# phi-brain4ch.net
KiCad netlist of a schematic drawn in EAGLE
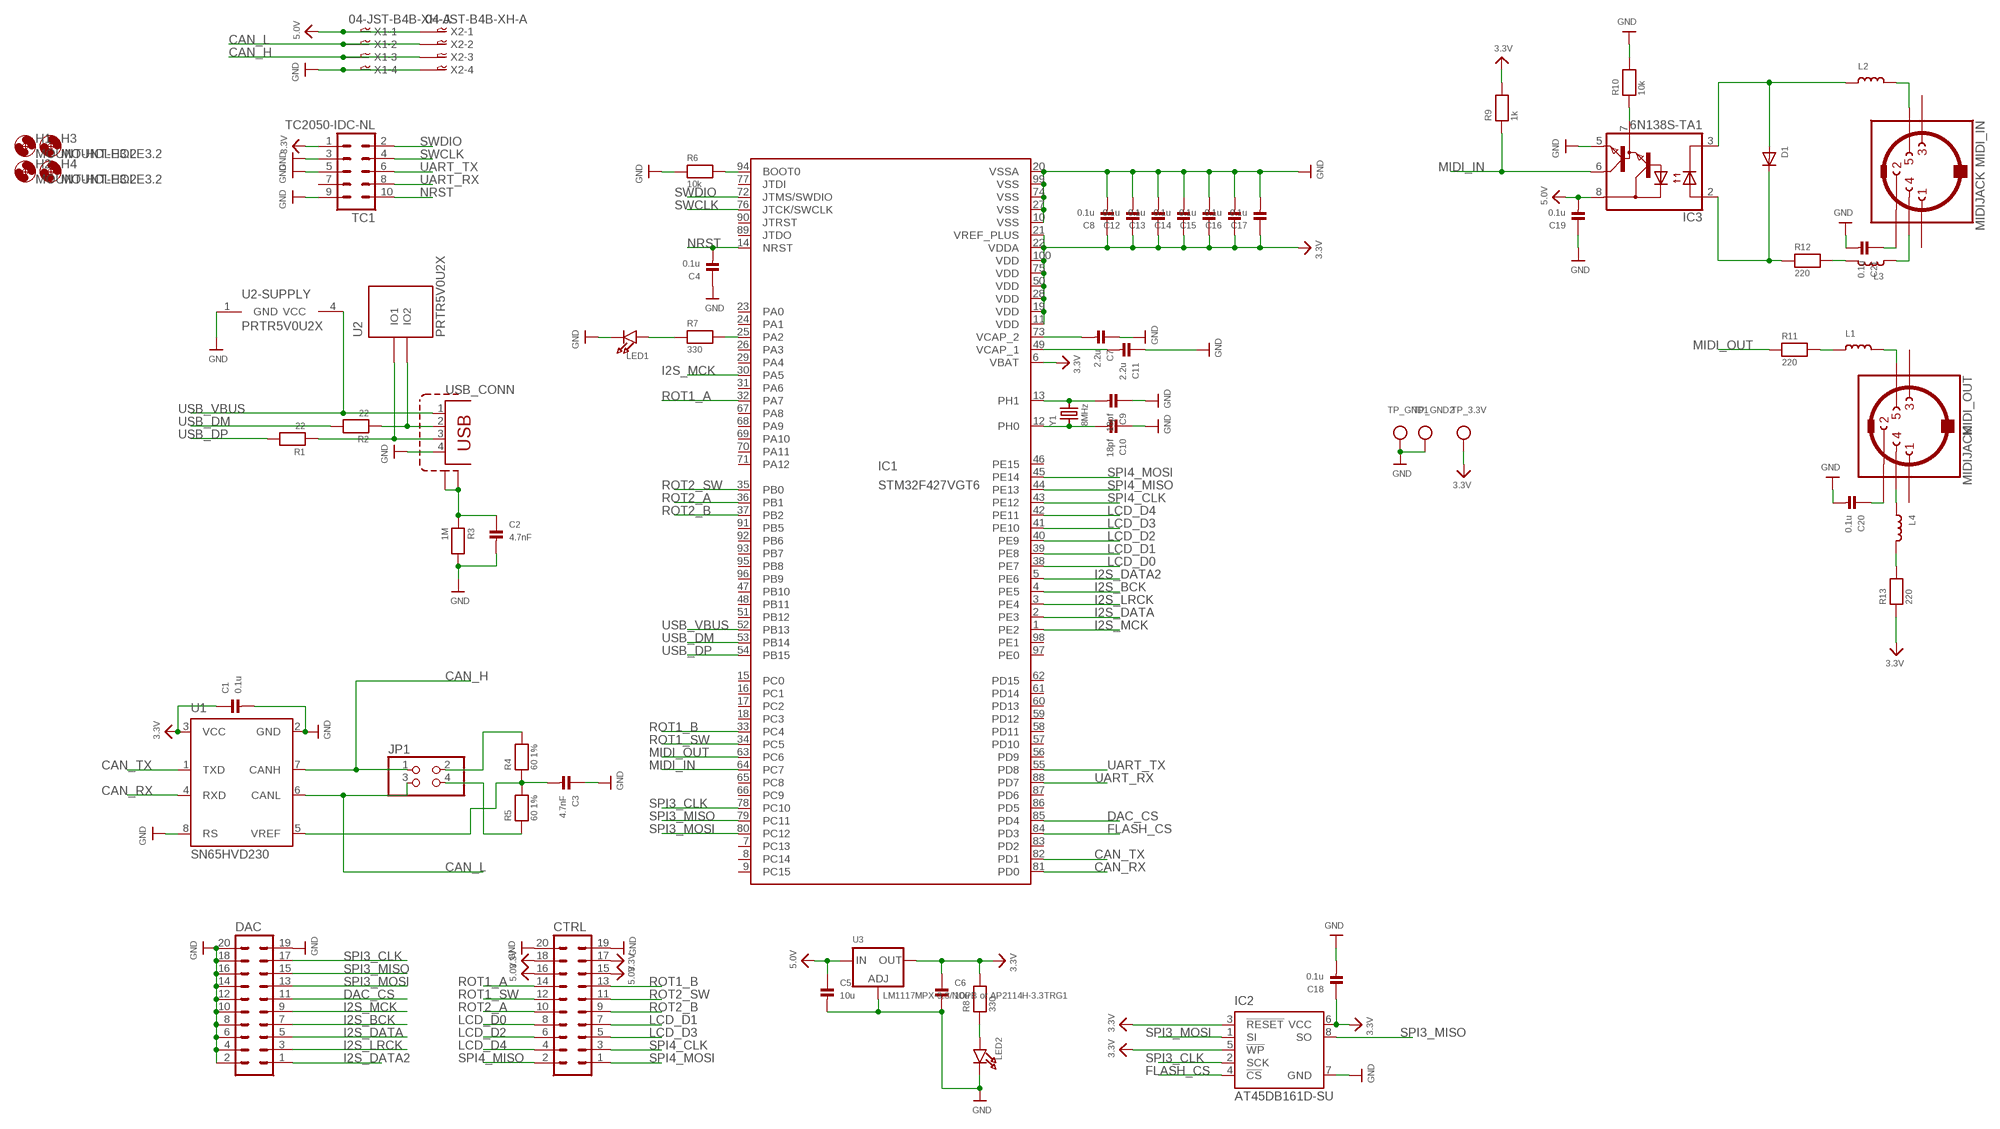
[diagram p0: schematic, sheet 1]

(export (version "E")
  (design (tool "Eeschema 10.0.6"))
  (components
    (comp (ref "C1")
      (value "0.1u")
      (footprint "eagle-import:0603")
      (fields (field (name "PARTNO") "0805DD104KAT2A"))
      (libsource (lib "eagle-import") (part "CAP_CERAMIC0603"))
    )
    (comp (ref "C2")
      (value "4.7nF")
      (footprint "eagle-import:0805")
      (fields (field (name "PARTNO") "885012207090"))
      (libsource (lib "eagle-import") (part "CAP_CERAMIC0805"))
    )
    (comp (ref "C3")
      (value "4.7nF")
      (footprint "eagle-import:0805")
      (fields (field (name "PARTNO") "885012207090"))
      (libsource (lib "eagle-import") (part "CAP_CERAMIC0805"))
    )
    (comp (ref "C4")
      (value "0.1u")
      (footprint "eagle-import:0603")
      (fields (field (name "PARTNO") "0805DD104KAT2A"))
      (libsource (lib "eagle-import") (part "CAP_CERAMIC0603"))
    )
    (comp (ref "C5")
      (value "10u")
      (footprint "eagle-import:0805")
      (fields (field (name "PARTNO") "81-GRM21BR6YA106KE3L"))
      (libsource (lib "eagle-import") (part "CAP_CERAMIC0805"))
    )
    (comp (ref "C6")
      (value "10u")
      (footprint "eagle-import:0805")
      (fields (field (name "PARTNO") "81-GRM21BR6YA106KE3L"))
      (libsource (lib "eagle-import") (part "CAP_CERAMIC0805"))
    )
    (comp (ref "C7")
      (value "2.2u")
      (footprint "eagle-import:0805")
      (fields (field (name "PARTNO") "581-08053D225MAT2A"))
      (libsource (lib "eagle-import") (part "CAP_CERAMIC0805"))
    )
    (comp (ref "C8")
      (value "0.1u")
      (footprint "eagle-import:0603")
      (fields (field (name "PARTNO") "0805DD104KAT2A"))
      (libsource (lib "eagle-import") (part "CAP_CERAMIC0603"))
    )
    (comp (ref "C9")
      (value "18pf")
      (footprint "eagle-import:0805")
      (fields (field (name "PARTNO") "C0805C180M3GACTU"))
      (libsource (lib "eagle-import") (part "CAP_CERAMIC0805"))
    )
    (comp (ref "C10")
      (value "18pf")
      (footprint "eagle-import:0805")
      (fields (field (name "PARTNO") "C0805C180M3GACTU"))
      (libsource (lib "eagle-import") (part "CAP_CERAMIC0805"))
    )
    (comp (ref "C11")
      (value "2.2u")
      (footprint "eagle-import:0805")
      (fields (field (name "PARTNO") "581-08053D225MAT2A"))
      (libsource (lib "eagle-import") (part "CAP_CERAMIC0805"))
    )
    (comp (ref "C12")
      (value "0.1u")
      (footprint "eagle-import:0603")
      (fields (field (name "PARTNO") "0805DD104KAT2A"))
      (libsource (lib "eagle-import") (part "CAP_CERAMIC0603"))
    )
    (comp (ref "C13")
      (value "0.1u")
      (footprint "eagle-import:0603")
      (fields (field (name "PARTNO") "0805DD104KAT2A"))
      (libsource (lib "eagle-import") (part "CAP_CERAMIC0603"))
    )
    (comp (ref "C14")
      (value "0.1u")
      (footprint "eagle-import:0603")
      (fields (field (name "PARTNO") "0805DD104KAT2A"))
      (libsource (lib "eagle-import") (part "CAP_CERAMIC0603"))
    )
    (comp (ref "C15")
      (value "0.1u")
      (footprint "eagle-import:0603")
      (fields (field (name "PARTNO") "0805DD104KAT2A"))
      (libsource (lib "eagle-import") (part "CAP_CERAMIC0603"))
    )
    (comp (ref "C16")
      (value "0.1u")
      (footprint "eagle-import:0603")
      (fields (field (name "PARTNO") "0805DD104KAT2A"))
      (libsource (lib "eagle-import") (part "CAP_CERAMIC0603"))
    )
    (comp (ref "C17")
      (value "0.1u")
      (footprint "eagle-import:0603")
      (fields (field (name "PARTNO") "0805DD104KAT2A"))
      (libsource (lib "eagle-import") (part "CAP_CERAMIC0603"))
    )
    (comp (ref "C18")
      (value "0.1u")
      (footprint "eagle-import:0603")
      (fields (field (name "PARTNO") "0805DD104KAT2A"))
      (libsource (lib "eagle-import") (part "CAP_CERAMIC0603"))
    )
    (comp (ref "C19")
      (value "0.1u")
      (footprint "eagle-import:0603")
      (fields (field (name "PARTNO") "0805DD104KAT2A"))
      (libsource (lib "eagle-import") (part "CAP_CERAMIC0603"))
    )
    (comp (ref "C20")
      (value "0.1u")
      (footprint "eagle-import:0603")
      (fields (field (name "PARTNO") "0805DD104KAT2A"))
      (libsource (lib "eagle-import") (part "CAP_CERAMIC0603"))
    )
    (comp (ref "C21")
      (value "0.1u")
      (footprint "eagle-import:0603")
      (fields (field (name "PARTNO") "0805DD104KAT2A"))
      (libsource (lib "eagle-import") (part "CAP_CERAMIC0603"))
    )
    (comp (ref "CTRL")
      (value "ML20")
      (footprint "eagle-import:ML20")
      (fields (field (name "PARTNO") "61202021621"))
      (libsource (lib "eagle-import") (part "ML20"))
    )
    (comp (ref "D1")
      (value "DIODESOD-123")
      (footprint "eagle-import:SOD-123")
      (fields (field (name "PARTNO") "MBR120"))
      (libsource (lib "eagle-import") (part "DIODESOD-123"))
    )
    (comp (ref "DAC")
      (value "ML20")
      (footprint "eagle-import:ML20")
      (fields (field (name "PARTNO") "61202021621"))
      (libsource (lib "eagle-import") (part "ML20"))
    )
    (comp (ref "H1")
      (value "MOUNT-HOLE3.2")
      (footprint "eagle-import:3,2")
      (libsource (lib "eagle-import") (part "MOUNT-HOLE3.2"))
    )
    (comp (ref "H2")
      (value "MOUNT-HOLE3.2")
      (footprint "eagle-import:3,2")
      (libsource (lib "eagle-import") (part "MOUNT-HOLE3.2"))
    )
    (comp (ref "H3")
      (value "MOUNT-HOLE3.2")
      (footprint "eagle-import:3,2")
      (libsource (lib "eagle-import") (part "MOUNT-HOLE3.2"))
    )
    (comp (ref "H4")
      (value "MOUNT-HOLE3.2")
      (footprint "eagle-import:3,2")
      (libsource (lib "eagle-import") (part "MOUNT-HOLE3.2"))
    )
    (comp (ref "IC1")
      (value "STM32F427VGT6")
      (footprint "eagle-import:TQFP100")
      (libsource (lib "eagle-import") (part "STM32F42X_43X_LQFP100"))
    )
    (comp (ref "IC2")
      (value "AT45DB161D-SU")
      (footprint "eagle-import:8S2")
      (fields (field (name "MF") "ATMEL"))
      (libsource (lib "eagle-import") (part "AT45DB161D-SU"))
    )
    (comp (ref "IC3")
      (value "6N138S-TA1")
      (footprint "eagle-import:SO8-GW300")
      (fields (field (name "PARTNO") "6N138S"))
      (libsource (lib "eagle-import") (part "6N138SMD"))
    )
    (comp (ref "JP1")
      (value "PINHD-2X2")
      (footprint "eagle-import:2X02")
      (fields (field (name "MPN") "5-146254-2"))
      (libsource (lib "eagle-import") (part "PINHD-2X2"))
    )
    (comp (ref "L1")
      (value "INDUCTOR0805")
      (footprint "eagle-import:0805")
      (fields (field (name "PARTNO") "70-ILHB0805ER601V"))
      (libsource (lib "eagle-import") (part "INDUCTOR0805"))
    )
    (comp (ref "L2")
      (value "INDUCTOR0805")
      (footprint "eagle-import:0805")
      (fields (field (name "PARTNO") "70-ILHB0805ER601V"))
      (libsource (lib "eagle-import") (part "INDUCTOR0805"))
    )
    (comp (ref "L3")
      (value "INDUCTOR0805")
      (footprint "eagle-import:0805")
      (fields (field (name "PARTNO") "70-ILHB0805ER601V"))
      (libsource (lib "eagle-import") (part "INDUCTOR0805"))
    )
    (comp (ref "L4")
      (value "INDUCTOR0805")
      (footprint "eagle-import:0805")
      (fields (field (name "PARTNO") "70-ILHB0805ER601V"))
      (libsource (lib "eagle-import") (part "INDUCTOR0805"))
    )
    (comp (ref "LED1")
      (value "LED0805")
      (footprint "eagle-import:CHIPLED_0805")
      (fields (field (name "PARTNO") "604-APT2012YC"))
      (libsource (lib "eagle-import") (part "LED0805"))
    )
    (comp (ref "LED2")
      (value "LED0805")
      (footprint "eagle-import:CHIPLED_0805")
      (fields (field (name "PARTNO") "604-APT2012YC"))
      (libsource (lib "eagle-import") (part "LED0805"))
    )
    (comp (ref "MIDI_IN")
      (value "MIDIJACK")
      (footprint "eagle-import:CP-2350")
      (libsource (lib "eagle-import") (part "MIDIJACK"))
    )
    (comp (ref "MIDI_OUT")
      (value "MIDIJACK")
      (footprint "eagle-import:CP-2350")
      (libsource (lib "eagle-import") (part "MIDIJACK"))
    )
    (comp (ref "R1")
      (value "22")
      (footprint "eagle-import:0805")
      (fields (field (name "MPN") "MF-RES-0603-22") (field (name "PARTNO") "ERJ-6ENF22R0V"))
      (libsource (lib "eagle-import") (part "RESISTOR0805"))
    )
    (comp (ref "R2")
      (value "22")
      (footprint "eagle-import:0805")
      (fields (field (name "MPN") "MF-RES-0603-22") (field (name "PARTNO") "ERJ-6ENF22R0V"))
      (libsource (lib "eagle-import") (part "RESISTOR0805"))
    )
    (comp (ref "R3")
      (value "1M")
      (footprint "eagle-import:0805")
      (fields (field (name "PARTNO") "AS08J1004ET"))
      (libsource (lib "eagle-import") (part "RESISTOR0805"))
    )
    (comp (ref "R4")
      (value "60 1%")
      (footprint "eagle-import:0805")
      (fields (field (name "MPN") "MF-RES-0603-60.4") (field (name "PARTNO") "ERJ-6ENF60R4V"))
      (libsource (lib "eagle-import") (part "RESISTOR0805"))
    )
    (comp (ref "R5")
      (value "60 1%")
      (footprint "eagle-import:0805")
      (fields (field (name "MPN") "MF-RES-0603-60.4") (field (name "PARTNO") "ERJ-6ENF60R4V"))
      (libsource (lib "eagle-import") (part "RESISTOR0805"))
    )
    (comp (ref "R6")
      (value "10k")
      (footprint "eagle-import:0805")
      (fields (field (name "PARTNO") "RC0805FR-0710KL"))
      (libsource (lib "eagle-import") (part "RESISTOR0805"))
    )
    (comp (ref "R7")
      (value "330")
      (footprint "eagle-import:0805")
      (fields (field (name "MPN") "MF-RES-0603-330") (field (name "PARTNO") "CPF0805B330RE1"))
      (libsource (lib "eagle-import") (part "RESISTOR0805"))
    )
    (comp (ref "R8")
      (value "330")
      (footprint "eagle-import:0805")
      (fields (field (name "MPN") "MF-RES-0603-330") (field (name "PARTNO") "CPF0805B330RE1"))
      (libsource (lib "eagle-import") (part "RESISTOR0805"))
    )
    (comp (ref "R9")
      (value "1k")
      (footprint "eagle-import:0805")
      (fields (field (name "PARTNO") "AS08J1001ET"))
      (libsource (lib "eagle-import") (part "RESISTOR0805"))
    )
    (comp (ref "R10")
      (value "10k")
      (footprint "eagle-import:0805")
      (fields (field (name "PARTNO") "RC0805FR-0710KL"))
      (libsource (lib "eagle-import") (part "RESISTOR0805"))
    )
    (comp (ref "R11")
      (value "220")
      (footprint "eagle-import:0805")
      (fields (field (name "PARTNO") "ERJ-6GEYJ221V"))
      (libsource (lib "eagle-import") (part "RESISTOR0805"))
    )
    (comp (ref "R12")
      (value "220")
      (footprint "eagle-import:0805")
      (fields (field (name "PARTNO") "ERJ-6GEYJ221V"))
      (libsource (lib "eagle-import") (part "RESISTOR0805"))
    )
    (comp (ref "R13")
      (value "220")
      (footprint "eagle-import:0805")
      (fields (field (name "PARTNO") "ERJ-6GEYJ221V"))
      (libsource (lib "eagle-import") (part "RESISTOR0805"))
    )
    (comp (ref "TC1")
      (value "TC2050-IDC-NL")
      (footprint "eagle-import:TC2050-IDC-NL")
      (libsource (lib "eagle-import") (part "TC2050-IDC-NL"))
    )
    (comp (ref "TP_3.3V")
      (value "TESTPOINT0.1\"")
      (footprint "eagle-import:1X01_ROUND")
      (libsource (lib "eagle-import") (part "TESTPOINT0.1{dblquote}"))
    )
    (comp (ref "TP_GND1")
      (value "TESTPOINT0.1\"")
      (footprint "eagle-import:1X01_ROUND")
      (libsource (lib "eagle-import") (part "TESTPOINT0.1{dblquote}"))
    )
    (comp (ref "TP_GND2")
      (value "TESTPOINT0.1\"")
      (footprint "eagle-import:1X01_ROUND")
      (libsource (lib "eagle-import") (part "TESTPOINT0.1{dblquote}"))
    )
    (comp (ref "U1")
      (value "SN65HVD230")
      (footprint "eagle-import:SO8")
      (fields (field (name "MPN") "SN65HVD230DR"))
      (libsource (lib "eagle-import") (part "SN65HVD230"))
    )
    (comp (ref "U2")
      (value "PRTR5V0U2X")
      (footprint "eagle-import:SOT-143B")
      (fields (field (name "MANUFACTURER") "NXP Semiconductors") (field (name "MPN") "PRTR5V0U2X,215"))
      (libsource (lib "eagle-import") (part "PRTR5V0U2X?"))
    )
    (comp (ref "U3")
      (value "LM1117MPX-3.3/NOPB or AP2114H-3.3TRG1")
      (footprint "eagle-import:SOT223-R")
      (fields (field (name "MPN") "LM1117MPX-3.3/NOPB"))
      (libsource (lib "eagle-import") (part "LM1117SOT223-REFLOW"))
    )
    (comp (ref "USB")
      (value "TE-292304-1")
      (footprint "eagle-import:TE-292304-1")
      (fields (field (name "MPN") "292304-1 ") (field (name "POPULATE") "0"))
      (libsource (lib "eagle-import") (part "TE-292304-1"))
    )
    (comp (ref "X1")
      (value "04-JST-B4B-XH-A")
      (footprint "eagle-import:B4B-XH")
      (fields (field (name "MPN") "B4B-XH-A(LF)(SN)"))
      (libsource (lib "eagle-import") (part "04-JST-B4B-XH-A"))
    )
    (comp (ref "X2")
      (value "04-JST-B4B-XH-A")
      (footprint "eagle-import:B4B-XH")
      (fields (field (name "MPN") "B4B-XH-A(LF)(SN)"))
      (libsource (lib "eagle-import") (part "04-JST-B4B-XH-A"))
    )
    (comp (ref "Y1")
      (value "8MHz")
      (footprint "eagle-import:HC49UP")
      (fields (field (name "PARTNO") "ABLS2-8.000MHz-B1U-T"))
      (libsource (lib "eagle-import") (part "CRYSTALSMD"))
    )
  )
  (nets
    (net (code "1") (name "/CAN_H") (class "Default")
      (node (ref "JP1") (pin "1") (pinfunction "1_1") (pintype "passive"))
      (node (ref "U1") (pin "7") (pinfunction "CANH_7") (pintype "bidirectional"))
      (node (ref "X1") (pin "P$3") (pinfunction "1_P$3") (pintype "passive"))
      (node (ref "X2") (pin "P$3") (pinfunction "1_P$3") (pintype "passive"))
    )
    (net (code "2") (name "/CAN_L") (class "Default")
      (node (ref "JP1") (pin "3") (pinfunction "3_3") (pintype "passive"))
      (node (ref "U1") (pin "6") (pinfunction "CANL_6") (pintype "bidirectional"))
      (node (ref "X1") (pin "P$2") (pinfunction "1_P$2") (pintype "passive"))
      (node (ref "X2") (pin "P$2") (pinfunction "1_P$2") (pintype "passive"))
    )
    (net (code "3") (name "/CAN_RX") (class "Default")
      (node (ref "IC1") (pin "81") (pinfunction "PD0_81") (pintype "bidirectional"))
      (node (ref "U1") (pin "4") (pinfunction "RXD_4") (pintype "output"))
    )
    (net (code "4") (name "/CAN_TX") (class "Default")
      (node (ref "IC1") (pin "82") (pinfunction "PD1_82") (pintype "bidirectional"))
      (node (ref "U1") (pin "1") (pinfunction "TXD_1") (pintype "input"))
    )
    (net (code "5") (name "/DAC_CS") (class "Default")
      (node (ref "DAC") (pin "11") (pinfunction "11_11") (pintype "passive"))
      (node (ref "IC1") (pin "85") (pinfunction "PD4_85") (pintype "bidirectional"))
    )
    (net (code "6") (name "/FLASH_CS") (class "Default")
      (node (ref "IC1") (pin "84") (pinfunction "PD3_84") (pintype "bidirectional"))
      (node (ref "IC2") (pin "4") (pinfunction "~{CS}_4") (pintype "input"))
    )
    (net (code "7") (name "/I2S_BCK") (class "Default")
      (node (ref "DAC") (pin "7") (pinfunction "7_7") (pintype "passive"))
      (node (ref "IC1") (pin "4") (pinfunction "PE5_4") (pintype "bidirectional"))
    )
    (net (code "8") (name "/I2S_DATA") (class "Default")
      (node (ref "DAC") (pin "5") (pinfunction "5_5") (pintype "passive"))
      (node (ref "IC1") (pin "2") (pinfunction "PE3_2") (pintype "bidirectional"))
    )
    (net (code "9") (name "/I2S_DATA2") (class "Default")
      (node (ref "DAC") (pin "1") (pinfunction "1_1") (pintype "passive"))
      (node (ref "IC1") (pin "5") (pinfunction "PE6_5") (pintype "bidirectional"))
    )
    (net (code "10") (name "/I2S_LRCK") (class "Default")
      (node (ref "DAC") (pin "3") (pinfunction "3_3") (pintype "passive"))
      (node (ref "IC1") (pin "3") (pinfunction "PE4_3") (pintype "bidirectional"))
    )
    (net (code "11") (name "/I2S_MCK") (class "Default")
      (node (ref "DAC") (pin "9") (pinfunction "9_9") (pintype "passive"))
      (node (ref "IC1") (pin "1") (pinfunction "PE2_1") (pintype "bidirectional"))
      (node (ref "IC1") (pin "30") (pinfunction "PA5_30") (pintype "bidirectional"))
    )
    (net (code "12") (name "/LCD_D0") (class "Default")
      (node (ref "CTRL") (pin "8") (pinfunction "8_8") (pintype "passive"))
      (node (ref "IC1") (pin "38") (pinfunction "PE7_38") (pintype "bidirectional"))
    )
    (net (code "13") (name "/LCD_D1") (class "Default")
      (node (ref "CTRL") (pin "7") (pinfunction "7_7") (pintype "passive"))
      (node (ref "IC1") (pin "39") (pinfunction "PE8_39") (pintype "bidirectional"))
    )
    (net (code "14") (name "/LCD_D2") (class "Default")
      (node (ref "CTRL") (pin "6") (pinfunction "6_6") (pintype "passive"))
      (node (ref "IC1") (pin "40") (pinfunction "PE9_40") (pintype "bidirectional"))
    )
    (net (code "15") (name "/LCD_D3") (class "Default")
      (node (ref "CTRL") (pin "5") (pinfunction "5_5") (pintype "passive"))
      (node (ref "IC1") (pin "41") (pinfunction "PE10_41") (pintype "bidirectional"))
    )
    (net (code "16") (name "/LCD_D4") (class "Default")
      (node (ref "CTRL") (pin "4") (pinfunction "4_4") (pintype "passive"))
      (node (ref "IC1") (pin "42") (pinfunction "PE11_42") (pintype "bidirectional"))
    )
    (net (code "17") (name "/MIDI_IN") (class "Default")
      (node (ref "IC1") (pin "64") (pinfunction "PC7_64") (pintype "bidirectional"))
      (node (ref "IC3") (pin "6") (pinfunction "VO_6") (pintype "passive"))
      (node (ref "R9") (pin "1") (pinfunction "1_1") (pintype "passive"))
    )
    (net (code "18") (name "/MIDI_OUT") (class "Default")
      (node (ref "IC1") (pin "63") (pinfunction "PC6_63") (pintype "bidirectional"))
      (node (ref "R11") (pin "1") (pinfunction "1_1") (pintype "passive"))
    )
    (net (code "19") (name "/NRST") (class "Default")
      (node (ref "C4") (pin "2") (pinfunction "P$2_2") (pintype "passive"))
      (node (ref "IC1") (pin "14") (pinfunction "NRST_14") (pintype "input"))
      (node (ref "TC1") (pin "10") (pinfunction "10_10") (pintype "passive"))
    )
    (net (code "20") (name "/ROT1_A") (class "Default")
      (node (ref "CTRL") (pin "14") (pinfunction "14_14") (pintype "passive"))
      (node (ref "IC1") (pin "32") (pinfunction "PA7_32") (pintype "bidirectional"))
    )
    (net (code "21") (name "/ROT1_B") (class "Default")
      (node (ref "CTRL") (pin "13") (pinfunction "13_13") (pintype "passive"))
      (node (ref "IC1") (pin "33") (pinfunction "PC4_33") (pintype "bidirectional"))
    )
    (net (code "22") (name "/ROT1_SW") (class "Default")
      (node (ref "CTRL") (pin "12") (pinfunction "12_12") (pintype "passive"))
      (node (ref "IC1") (pin "34") (pinfunction "PC5_34") (pintype "bidirectional"))
    )
    (net (code "23") (name "/ROT2_A") (class "Default")
      (node (ref "CTRL") (pin "10") (pinfunction "10_10") (pintype "passive"))
      (node (ref "IC1") (pin "36") (pinfunction "PB1_36") (pintype "bidirectional"))
    )
    (net (code "24") (name "/ROT2_B") (class "Default")
      (node (ref "CTRL") (pin "9") (pinfunction "9_9") (pintype "passive"))
      (node (ref "IC1") (pin "37") (pinfunction "PB2_37") (pintype "bidirectional"))
    )
    (net (code "25") (name "/ROT2_SW") (class "Default")
      (node (ref "CTRL") (pin "11") (pinfunction "11_11") (pintype "passive"))
      (node (ref "IC1") (pin "35") (pinfunction "PB0_35") (pintype "bidirectional"))
    )
    (net (code "26") (name "/SPI3_CLK") (class "Default")
      (node (ref "DAC") (pin "17") (pinfunction "17_17") (pintype "passive"))
      (node (ref "IC1") (pin "78") (pinfunction "PC10_78") (pintype "bidirectional"))
      (node (ref "IC2") (pin "2") (pinfunction "SCK_2") (pintype "input"))
    )
    (net (code "27") (name "/SPI3_MISO") (class "Default")
      (node (ref "DAC") (pin "15") (pinfunction "15_15") (pintype "passive"))
      (node (ref "IC1") (pin "79") (pinfunction "PC11_79") (pintype "bidirectional"))
      (node (ref "IC2") (pin "8") (pinfunction "SO_8") (pintype "output"))
    )
    (net (code "28") (name "/SPI3_MOSI") (class "Default")
      (node (ref "DAC") (pin "13") (pinfunction "13_13") (pintype "passive"))
      (node (ref "IC1") (pin "80") (pinfunction "PC12_80") (pintype "bidirectional"))
      (node (ref "IC2") (pin "1") (pinfunction "SI_1") (pintype "input"))
    )
    (net (code "29") (name "/SPI4_CLK") (class "Default")
      (node (ref "CTRL") (pin "3") (pinfunction "3_3") (pintype "passive"))
      (node (ref "IC1") (pin "43") (pinfunction "PE12_43") (pintype "bidirectional"))
    )
    (net (code "30") (name "/SPI4_MISO") (class "Default")
      (node (ref "CTRL") (pin "2") (pinfunction "2_2") (pintype "passive"))
      (node (ref "IC1") (pin "44") (pinfunction "PE13_44") (pintype "bidirectional"))
    )
    (net (code "31") (name "/SPI4_MOSI") (class "Default")
      (node (ref "CTRL") (pin "1") (pinfunction "1_1") (pintype "passive"))
      (node (ref "IC1") (pin "45") (pinfunction "PE14_45") (pintype "bidirectional"))
    )
    (net (code "32") (name "/SWCLK") (class "Default")
      (node (ref "IC1") (pin "76") (pinfunction "JTCK/SWCLK_76") (pintype "input"))
      (node (ref "TC1") (pin "4") (pinfunction "4_4") (pintype "passive"))
    )
    (net (code "33") (name "/SWDIO") (class "Default")
      (node (ref "IC1") (pin "72") (pinfunction "JTMS/SWDIO_72") (pintype "input"))
      (node (ref "TC1") (pin "2") (pinfunction "2_2") (pintype "passive"))
    )
    (net (code "34") (name "/UART_RX") (class "Default")
      (node (ref "IC1") (pin "88") (pinfunction "PD7_88") (pintype "bidirectional"))
      (node (ref "TC1") (pin "8") (pinfunction "8_8") (pintype "passive"))
    )
    (net (code "35") (name "/UART_TX") (class "Default")
      (node (ref "IC1") (pin "55") (pinfunction "PD8_55") (pintype "bidirectional"))
      (node (ref "TC1") (pin "6") (pinfunction "6_6") (pintype "passive"))
    )
    (net (code "36") (name "/USB_DM") (class "Default")
      (node (ref "IC1") (pin "53") (pinfunction "PB14_53") (pintype "bidirectional"))
      (node (ref "R2") (pin "2") (pinfunction "2_2") (pintype "passive"))
    )
    (net (code "37") (name "/USB_DP") (class "Default")
      (node (ref "IC1") (pin "54") (pinfunction "PB15_54") (pintype "bidirectional"))
      (node (ref "R1") (pin "2") (pinfunction "2_2") (pintype "passive"))
    )
    (net (code "38") (name "/USB_VBUS") (class "Default")
      (node (ref "IC1") (pin "52") (pinfunction "PB13_52") (pintype "bidirectional"))
      (node (ref "U2") (pin "4") (pinfunction "VCC_4") (pintype "bidirectional"))
      (node (ref "USB") (pin "1") (pinfunction "1_1") (pintype "bidirectional"))
    )
    (net (code "39") (name "3.3V") (class "Default")
      (node (ref "C1") (pin "1") (pinfunction "P$1_1") (pintype "passive"))
      (node (ref "C12") (pin "1") (pinfunction "P$1_1") (pintype "passive"))
      (node (ref "C13") (pin "1") (pinfunction "P$1_1") (pintype "passive"))
      (node (ref "C14") (pin "1") (pinfunction "P$1_1") (pintype "passive"))
      (node (ref "C15") (pin "1") (pinfunction "P$1_1") (pintype "passive"))
      (node (ref "C16") (pin "1") (pinfunction "P$1_1") (pintype "passive"))
      (node (ref "C17") (pin "1") (pinfunction "P$1_1") (pintype "passive"))
      (node (ref "C18") (pin "1") (pinfunction "P$1_1") (pintype "passive"))
      (node (ref "C6") (pin "1") (pinfunction "P$1_1") (pintype "passive"))
      (node (ref "C8") (pin "1") (pinfunction "P$1_1") (pintype "passive"))
      (node (ref "CTRL") (pin "17") (pinfunction "17_17") (pintype "passive"))
      (node (ref "CTRL") (pin "18") (pinfunction "18_18") (pintype "passive"))
      (node (ref "IC1") (pin "100") (pinfunction "VDD_100") (pintype "power_in"))
      (node (ref "IC1") (pin "11") (pinfunction "VDD_11") (pintype "power_in"))
      (node (ref "IC1") (pin "19") (pinfunction "VDD_19") (pintype "power_in"))
      (node (ref "IC1") (pin "21") (pinfunction "VREF_PLUS_21") (pintype "passive"))
      (node (ref "IC1") (pin "22") (pinfunction "VDDA_22") (pintype "power_in"))
      (node (ref "IC1") (pin "28") (pinfunction "VDD_28") (pintype "power_in"))
      (node (ref "IC1") (pin "50") (pinfunction "VDD_50") (pintype "power_in"))
      (node (ref "IC1") (pin "6") (pinfunction "VBAT_6") (pintype "passive"))
      (node (ref "IC1") (pin "75") (pinfunction "VDD_75") (pintype "power_in"))
      (node (ref "IC2") (pin "3") (pinfunction "~{RESET}_3") (pintype "input"))
      (node (ref "IC2") (pin "5") (pinfunction "~{WP}_5") (pintype "input"))
      (node (ref "IC2") (pin "6") (pinfunction "VCC_6") (pintype "power_in"))
      (node (ref "R13") (pin "1") (pinfunction "1_1") (pintype "passive"))
      (node (ref "R8") (pin "2") (pinfunction "2_2") (pintype "passive"))
      (node (ref "R9") (pin "2") (pinfunction "2_2") (pintype "passive"))
      (node (ref "TC1") (pin "1") (pinfunction "1_1") (pintype "passive"))
      (node (ref "TP_3.3V") (pin "1") (pinfunction "P$1_1") (pintype "bidirectional"))
      (node (ref "U1") (pin "3") (pinfunction "VCC_3") (pintype "power_in"))
      (node (ref "U3") (pin "2") (pinfunction "OUT_2") (pintype "passive"))
    )
    (net (code "40") (name "5.0V") (class "Default")
      (node (ref "C19") (pin "2") (pinfunction "P$2_2") (pintype "passive"))
      (node (ref "C5") (pin "1") (pinfunction "P$1_1") (pintype "passive"))
      (node (ref "CTRL") (pin "15") (pinfunction "15_15") (pintype "passive"))
      (node (ref "CTRL") (pin "16") (pinfunction "16_16") (pintype "passive"))
      (node (ref "IC3") (pin "8") (pinfunction "VCC_8") (pintype "passive"))
      (node (ref "U3") (pin "3") (pinfunction "IN_3") (pintype "input"))
      (node (ref "X1") (pin "P$1") (pinfunction "1_P$1") (pintype "passive"))
      (node (ref "X2") (pin "P$1") (pinfunction "1_P$1") (pintype "passive"))
    )
    (net (code "41") (name "GND") (class "Default")
      (node (ref "C1") (pin "2") (pinfunction "P$2_2") (pintype "passive"))
      (node (ref "C10") (pin "1") (pinfunction "P$1_1") (pintype "passive"))
      (node (ref "C11") (pin "1") (pinfunction "P$1_1") (pintype "passive"))
      (node (ref "C12") (pin "2") (pinfunction "P$2_2") (pintype "passive"))
      (node (ref "C13") (pin "2") (pinfunction "P$2_2") (pintype "passive"))
      (node (ref "C14") (pin "2") (pinfunction "P$2_2") (pintype "passive"))
      (node (ref "C15") (pin "2") (pinfunction "P$2_2") (pintype "passive"))
      (node (ref "C16") (pin "2") (pinfunction "P$2_2") (pintype "passive"))
      (node (ref "C17") (pin "2") (pinfunction "P$2_2") (pintype "passive"))
      (node (ref "C18") (pin "2") (pinfunction "P$2_2") (pintype "passive"))
      (node (ref "C19") (pin "1") (pinfunction "P$1_1") (pintype "passive"))
      (node (ref "C2") (pin "2") (pinfunction "P$2_2") (pintype "passive"))
      (node (ref "C20") (pin "2") (pinfunction "P$2_2") (pintype "passive"))
      (node (ref "C21") (pin "2") (pinfunction "P$2_2") (pintype "passive"))
      (node (ref "C3") (pin "1") (pinfunction "P$1_1") (pintype "passive"))
      (node (ref "C4") (pin "1") (pinfunction "P$1_1") (pintype "passive"))
      (node (ref "C5") (pin "2") (pinfunction "P$2_2") (pintype "passive"))
      (node (ref "C6") (pin "2") (pinfunction "P$2_2") (pintype "passive"))
      (node (ref "C7") (pin "1") (pinfunction "P$1_1") (pintype "passive"))
      (node (ref "C8") (pin "2") (pinfunction "P$2_2") (pintype "passive"))
      (node (ref "C9") (pin "1") (pinfunction "P$1_1") (pintype "passive"))
      (node (ref "CTRL") (pin "19") (pinfunction "19_19") (pintype "passive"))
      (node (ref "CTRL") (pin "20") (pinfunction "20_20") (pintype "passive"))
      (node (ref "DAC") (pin "10") (pinfunction "10_10") (pintype "passive"))
      (node (ref "DAC") (pin "12") (pinfunction "12_12") (pintype "passive"))
      (node (ref "DAC") (pin "14") (pinfunction "14_14") (pintype "passive"))
      (node (ref "DAC") (pin "16") (pinfunction "16_16") (pintype "passive"))
      (node (ref "DAC") (pin "18") (pinfunction "18_18") (pintype "passive"))
      (node (ref "DAC") (pin "19") (pinfunction "19_19") (pintype "passive"))
      (node (ref "DAC") (pin "2") (pinfunction "2_2") (pintype "passive"))
      (node (ref "DAC") (pin "20") (pinfunction "20_20") (pintype "passive"))
      (node (ref "DAC") (pin "4") (pinfunction "4_4") (pintype "passive"))
      (node (ref "DAC") (pin "6") (pinfunction "6_6") (pintype "passive"))
      (node (ref "DAC") (pin "8") (pinfunction "8_8") (pintype "passive"))
      (node (ref "IC1") (pin "10") (pinfunction "VSS_10") (pintype "power_in"))
      (node (ref "IC1") (pin "20") (pinfunction "VSSA_20") (pintype "power_in"))
      (node (ref "IC1") (pin "27") (pinfunction "VSS_27") (pintype "power_in"))
      (node (ref "IC1") (pin "74") (pinfunction "VSS_74") (pintype "power_in"))
      (node (ref "IC1") (pin "99") (pinfunction "VSS_99") (pintype "power_in"))
      (node (ref "IC2") (pin "7") (pinfunction "GND_7") (pintype "power_in"))
      (node (ref "IC3") (pin "5") (pinfunction "GND_5") (pintype "passive"))
      (node (ref "LED1") (pin "C") (pinfunction "C_C") (pintype "passive"))
      (node (ref "LED2") (pin "C") (pinfunction "C_C") (pintype "passive"))
      (node (ref "R10") (pin "2") (pinfunction "2_2") (pintype "passive"))
      (node (ref "R3") (pin "2") (pinfunction "2_2") (pintype "passive"))
      (node (ref "R6") (pin "1") (pinfunction "1_1") (pintype "passive"))
      (node (ref "TC1") (pin "3") (pinfunction "3_3") (pintype "passive"))
      (node (ref "TC1") (pin "5") (pinfunction "5_5") (pintype "passive"))
      (node (ref "TC1") (pin "9") (pinfunction "9_9") (pintype "passive"))
      (node (ref "TP_GND1") (pin "1") (pinfunction "P$1_1") (pintype "bidirectional"))
      (node (ref "TP_GND2") (pin "1") (pinfunction "P$1_1") (pintype "bidirectional"))
      (node (ref "U1") (pin "2") (pinfunction "GND_2") (pintype "power_in"))
      (node (ref "U1") (pin "8") (pinfunction "RS_8") (pintype "input"))
      (node (ref "U2") (pin "1") (pinfunction "GND_1") (pintype "bidirectional"))
      (node (ref "U3") (pin "1") (pinfunction "ADJ_1") (pintype "input"))
      (node (ref "USB") (pin "4") (pinfunction "4_4") (pintype "bidirectional"))
      (node (ref "X1") (pin "P$4") (pinfunction "1_P$4") (pintype "passive"))
      (node (ref "X2") (pin "P$4") (pinfunction "1_P$4") (pintype "passive"))
    )
    (net (code "42") (name "Net-(C2-P$1)") (class "Default")
      (node (ref "C2") (pin "1") (pinfunction "P$1_1") (pintype "passive"))
      (node (ref "R3") (pin "1") (pinfunction "1_1") (pintype "passive"))
      (node (ref "USB") (pin "P$1") (pinfunction "S1_P$1") (pintype "passive"))
      (node (ref "USB") (pin "P$2") (pinfunction "S2_P$2") (pintype "passive"))
    )
    (net (code "43") (name "Net-(C3-P$2)") (class "Default")
      (node (ref "C3") (pin "2") (pinfunction "P$2_2") (pintype "passive"))
      (node (ref "R4") (pin "1") (pinfunction "1_1") (pintype "passive"))
      (node (ref "R5") (pin "2") (pinfunction "2_2") (pintype "passive"))
      (node (ref "U1") (pin "5") (pinfunction "VREF_5") (pintype "output"))
    )
    (net (code "44") (name "Net-(C7-P$2)") (class "Default")
      (node (ref "C7") (pin "2") (pinfunction "P$2_2") (pintype "passive"))
      (node (ref "IC1") (pin "73") (pinfunction "VCAP_2_73") (pintype "passive"))
    )
    (net (code "45") (name "Net-(C9-P$2)") (class "Default")
      (node (ref "C9") (pin "2") (pinfunction "P$2_2") (pintype "passive"))
      (node (ref "IC1") (pin "13") (pinfunction "PH1_13") (pintype "bidirectional"))
      (node (ref "Y1") (pin "2") (pinfunction "2_2") (pintype "passive"))
    )
    (net (code "46") (name "Net-(C10-P$2)") (class "Default")
      (node (ref "C10") (pin "2") (pinfunction "P$2_2") (pintype "passive"))
      (node (ref "IC1") (pin "12") (pinfunction "PH0_12") (pintype "bidirectional"))
      (node (ref "Y1") (pin "1") (pinfunction "1_1") (pintype "passive"))
    )
    (net (code "47") (name "Net-(C11-P$2)") (class "Default")
      (node (ref "C11") (pin "2") (pinfunction "P$2_2") (pintype "passive"))
      (node (ref "IC1") (pin "49") (pinfunction "VCAP_1_49") (pintype "passive"))
    )
    (net (code "48") (name "Net-(C20-P$1)") (class "Default")
      (node (ref "C20") (pin "1") (pinfunction "P$1_1") (pintype "passive"))
      (node (ref "MIDI_OUT") (pin "2") (pinfunction "2_2") (pintype "passive"))
    )
    (net (code "49") (name "Net-(C21-P$1)") (class "Default")
      (node (ref "C21") (pin "1") (pinfunction "P$1_1") (pintype "passive"))
      (node (ref "MIDI_IN") (pin "2") (pinfunction "2_2") (pintype "passive"))
    )
    (net (code "50") (name "Net-(IC1-BOOT0)") (class "Default")
      (node (ref "IC1") (pin "94") (pinfunction "BOOT0_94") (pintype "input"))
      (node (ref "R6") (pin "2") (pinfunction "2_2") (pintype "passive"))
    )
    (net (code "51") (name "Net-(IC1-PA2)") (class "Default")
      (node (ref "IC1") (pin "25") (pinfunction "PA2_25") (pintype "bidirectional"))
      (node (ref "R7") (pin "2") (pinfunction "2_2") (pintype "passive"))
    )
    (net (code "52") (name "Net-(IC3-A)") (class "Default")
      (node (ref "D1") (pin "C") (pinfunction "C_C") (pintype "passive"))
      (node (ref "IC3") (pin "2") (pinfunction "A_2") (pintype "passive"))
      (node (ref "R12") (pin "1") (pinfunction "1_1") (pintype "passive"))
    )
    (net (code "53") (name "Net-(IC3-C)") (class "Default")
      (node (ref "D1") (pin "A") (pinfunction "A_A") (pintype "passive"))
      (node (ref "IC3") (pin "3") (pinfunction "C_3") (pintype "passive"))
      (node (ref "L2") (pin "1") (pinfunction "1_1") (pintype "passive"))
    )
    (net (code "54") (name "Net-(IC3-VB)") (class "Default")
      (node (ref "IC3") (pin "7") (pinfunction "VB_7") (pintype "passive"))
      (node (ref "R10") (pin "1") (pinfunction "1_1") (pintype "passive"))
    )
    (net (code "55") (name "Net-(JP1-Pad2)") (class "Default")
      (node (ref "JP1") (pin "2") (pinfunction "2_2") (pintype "passive"))
      (node (ref "R4") (pin "2") (pinfunction "2_2") (pintype "passive"))
    )
    (net (code "56") (name "Net-(JP1-Pad4)") (class "Default")
      (node (ref "JP1") (pin "4") (pinfunction "4_4") (pintype "passive"))
      (node (ref "R5") (pin "1") (pinfunction "1_1") (pintype "passive"))
    )
    (net (code "57") (name "Net-(L1-Pad1)") (class "Default")
      (node (ref "L1") (pin "1") (pinfunction "1_1") (pintype "passive"))
      (node (ref "R11") (pin "2") (pinfunction "2_2") (pintype "passive"))
    )
    (net (code "58") (name "Net-(L1-Pad2)") (class "Default")
      (node (ref "L1") (pin "2") (pinfunction "2_2") (pintype "passive"))
      (node (ref "MIDI_OUT") (pin "5") (pinfunction "5_5") (pintype "passive"))
    )
    (net (code "59") (name "Net-(L2-Pad2)") (class "Default")
      (node (ref "L2") (pin "2") (pinfunction "2_2") (pintype "passive"))
      (node (ref "MIDI_IN") (pin "5") (pinfunction "5_5") (pintype "passive"))
    )
    (net (code "60") (name "Net-(L3-Pad1)") (class "Default")
      (node (ref "L3") (pin "1") (pinfunction "1_1") (pintype "passive"))
      (node (ref "MIDI_IN") (pin "4") (pinfunction "4_4") (pintype "passive"))
    )
    (net (code "61") (name "Net-(L3-Pad2)") (class "Default")
      (node (ref "L3") (pin "2") (pinfunction "2_2") (pintype "passive"))
      (node (ref "R12") (pin "2") (pinfunction "2_2") (pintype "passive"))
    )
    (net (code "62") (name "Net-(L4-Pad1)") (class "Default")
      (node (ref "L4") (pin "1") (pinfunction "1_1") (pintype "passive"))
      (node (ref "MIDI_OUT") (pin "4") (pinfunction "4_4") (pintype "passive"))
    )
    (net (code "63") (name "Net-(L4-Pad2)") (class "Default")
      (node (ref "L4") (pin "2") (pinfunction "2_2") (pintype "passive"))
      (node (ref "R13") (pin "2") (pinfunction "2_2") (pintype "passive"))
    )
    (net (code "64") (name "Net-(LED1-PadA)") (class "Default")
      (node (ref "LED1") (pin "A") (pinfunction "A_A") (pintype "passive"))
      (node (ref "R7") (pin "1") (pinfunction "1_1") (pintype "passive"))
    )
    (net (code "65") (name "Net-(LED2-PadA)") (class "Default")
      (node (ref "LED2") (pin "A") (pinfunction "A_A") (pintype "passive"))
      (node (ref "R8") (pin "1") (pinfunction "1_1") (pintype "passive"))
    )
    (net (code "66") (name "Net-(U2B-IO1)") (class "Default")
      (node (ref "R1") (pin "1") (pinfunction "1_1") (pintype "passive"))
      (node (ref "U2") (pin "2") (pinfunction "IO1_2") (pintype "bidirectional"))
      (node (ref "USB") (pin "3") (pinfunction "3_3") (pintype "bidirectional"))
    )
    (net (code "67") (name "Net-(U2B-IO2)") (class "Default")
      (node (ref "R2") (pin "1") (pinfunction "1_1") (pintype "passive"))
      (node (ref "U2") (pin "3") (pinfunction "IO2_3") (pintype "bidirectional"))
      (node (ref "USB") (pin "2") (pinfunction "2_2") (pintype "bidirectional"))
    )
    (net (code "68") (name "unconnected-(IC1-JTDI-Pad77)") (class "Default")
      (node (ref "IC1") (pin "77") (pinfunction "JTDI_77") (pintype "input"))
    )
    (net (code "69") (name "unconnected-(IC1-JTDO-Pad89)") (class "Default")
      (node (ref "IC1") (pin "89") (pinfunction "JTDO_89") (pintype "output"))
    )
    (net (code "70") (name "unconnected-(IC1-JTRST-Pad90)") (class "Default")
      (node (ref "IC1") (pin "90") (pinfunction "JTRST_90") (pintype "input"))
    )
    (net (code "71") (name "unconnected-(IC1-PA0-Pad23)") (class "Default")
      (node (ref "IC1") (pin "23") (pinfunction "PA0_23") (pintype "bidirectional"))
    )
    (net (code "72") (name "unconnected-(IC1-PA1-Pad24)") (class "Default")
      (node (ref "IC1") (pin "24") (pinfunction "PA1_24") (pintype "bidirectional"))
    )
    (net (code "73") (name "unconnected-(IC1-PA3-Pad26)") (class "Default")
      (node (ref "IC1") (pin "26") (pinfunction "PA3_26") (pintype "bidirectional"))
    )
    (net (code "74") (name "unconnected-(IC1-PA4-Pad29)") (class "Default")
      (node (ref "IC1") (pin "29") (pinfunction "PA4_29") (pintype "bidirectional"))
    )
    (net (code "75") (name "unconnected-(IC1-PA6-Pad31)") (class "Default")
      (node (ref "IC1") (pin "31") (pinfunction "PA6_31") (pintype "bidirectional"))
    )
    (net (code "76") (name "unconnected-(IC1-PA8-Pad67)") (class "Default")
      (node (ref "IC1") (pin "67") (pinfunction "PA8_67") (pintype "bidirectional"))
    )
    (net (code "77") (name "unconnected-(IC1-PA9-Pad68)") (class "Default")
      (node (ref "IC1") (pin "68") (pinfunction "PA9_68") (pintype "bidirectional"))
    )
    (net (code "78") (name "unconnected-(IC1-PA10-Pad69)") (class "Default")
      (node (ref "IC1") (pin "69") (pinfunction "PA10_69") (pintype "bidirectional"))
    )
    (net (code "79") (name "unconnected-(IC1-PA11-Pad70)") (class "Default")
      (node (ref "IC1") (pin "70") (pinfunction "PA11_70") (pintype "bidirectional"))
    )
    (net (code "80") (name "unconnected-(IC1-PA12-Pad71)") (class "Default")
      (node (ref "IC1") (pin "71") (pinfunction "PA12_71") (pintype "bidirectional"))
    )
    (net (code "81") (name "unconnected-(IC1-PB5-Pad91)") (class "Default")
      (node (ref "IC1") (pin "91") (pinfunction "PB5_91") (pintype "bidirectional"))
    )
    (net (code "82") (name "unconnected-(IC1-PB6-Pad92)") (class "Default")
      (node (ref "IC1") (pin "92") (pinfunction "PB6_92") (pintype "bidirectional"))
    )
    (net (code "83") (name "unconnected-(IC1-PB7-Pad93)") (class "Default")
      (node (ref "IC1") (pin "93") (pinfunction "PB7_93") (pintype "bidirectional"))
    )
    (net (code "84") (name "unconnected-(IC1-PB8-Pad95)") (class "Default")
      (node (ref "IC1") (pin "95") (pinfunction "PB8_95") (pintype "bidirectional"))
    )
    (net (code "85") (name "unconnected-(IC1-PB9-Pad96)") (class "Default")
      (node (ref "IC1") (pin "96") (pinfunction "PB9_96") (pintype "bidirectional"))
    )
    (net (code "86") (name "unconnected-(IC1-PB10-Pad47)") (class "Default")
      (node (ref "IC1") (pin "47") (pinfunction "PB10_47") (pintype "bidirectional"))
    )
    (net (code "87") (name "unconnected-(IC1-PB11-Pad48)") (class "Default")
      (node (ref "IC1") (pin "48") (pinfunction "PB11_48") (pintype "bidirectional"))
    )
    (net (code "88") (name "unconnected-(IC1-PB12-Pad51)") (class "Default")
      (node (ref "IC1") (pin "51") (pinfunction "PB12_51") (pintype "bidirectional"))
    )
    (net (code "89") (name "unconnected-(IC1-PC0-Pad15)") (class "Default")
      (node (ref "IC1") (pin "15") (pinfunction "PC0_15") (pintype "bidirectional"))
    )
    (net (code "90") (name "unconnected-(IC1-PC1-Pad16)") (class "Default")
      (node (ref "IC1") (pin "16") (pinfunction "PC1_16") (pintype "bidirectional"))
    )
    (net (code "91") (name "unconnected-(IC1-PC2-Pad17)") (class "Default")
      (node (ref "IC1") (pin "17") (pinfunction "PC2_17") (pintype "bidirectional"))
    )
    (net (code "92") (name "unconnected-(IC1-PC3-Pad18)") (class "Default")
      (node (ref "IC1") (pin "18") (pinfunction "PC3_18") (pintype "bidirectional"))
    )
    (net (code "93") (name "unconnected-(IC1-PC8-Pad65)") (class "Default")
      (node (ref "IC1") (pin "65") (pinfunction "PC8_65") (pintype "bidirectional"))
    )
    (net (code "94") (name "unconnected-(IC1-PC9-Pad66)") (class "Default")
      (node (ref "IC1") (pin "66") (pinfunction "PC9_66") (pintype "bidirectional"))
    )
    (net (code "95") (name "unconnected-(IC1-PC13-Pad7)") (class "Default")
      (node (ref "IC1") (pin "7") (pinfunction "PC13_7") (pintype "bidirectional"))
    )
    (net (code "96") (name "unconnected-(IC1-PC14-Pad8)") (class "Default")
      (node (ref "IC1") (pin "8") (pinfunction "PC14_8") (pintype "bidirectional"))
    )
    (net (code "97") (name "unconnected-(IC1-PC15-Pad9)") (class "Default")
      (node (ref "IC1") (pin "9") (pinfunction "PC15_9") (pintype "bidirectional"))
    )
    (net (code "98") (name "unconnected-(IC1-PD2-Pad83)") (class "Default")
      (node (ref "IC1") (pin "83") (pinfunction "PD2_83") (pintype "bidirectional"))
    )
    (net (code "99") (name "unconnected-(IC1-PD5-Pad86)") (class "Default")
      (node (ref "IC1") (pin "86") (pinfunction "PD5_86") (pintype "bidirectional"))
    )
    (net (code "100") (name "unconnected-(IC1-PD6-Pad87)") (class "Default")
      (node (ref "IC1") (pin "87") (pinfunction "PD6_87") (pintype "bidirectional"))
    )
    (net (code "101") (name "unconnected-(IC1-PD9-Pad56)") (class "Default")
      (node (ref "IC1") (pin "56") (pinfunction "PD9_56") (pintype "bidirectional"))
    )
    (net (code "102") (name "unconnected-(IC1-PD10-Pad57)") (class "Default")
      (node (ref "IC1") (pin "57") (pinfunction "PD10_57") (pintype "bidirectional"))
    )
    (net (code "103") (name "unconnected-(IC1-PD11-Pad58)") (class "Default")
      (node (ref "IC1") (pin "58") (pinfunction "PD11_58") (pintype "bidirectional"))
    )
    (net (code "104") (name "unconnected-(IC1-PD12-Pad59)") (class "Default")
      (node (ref "IC1") (pin "59") (pinfunction "PD12_59") (pintype "bidirectional"))
    )
    (net (code "105") (name "unconnected-(IC1-PD13-Pad60)") (class "Default")
      (node (ref "IC1") (pin "60") (pinfunction "PD13_60") (pintype "bidirectional"))
    )
    (net (code "106") (name "unconnected-(IC1-PD14-Pad61)") (class "Default")
      (node (ref "IC1") (pin "61") (pinfunction "PD14_61") (pintype "bidirectional"))
    )
    (net (code "107") (name "unconnected-(IC1-PD15-Pad62)") (class "Default")
      (node (ref "IC1") (pin "62") (pinfunction "PD15_62") (pintype "bidirectional"))
    )
    (net (code "108") (name "unconnected-(IC1-PE0-Pad97)") (class "Default")
      (node (ref "IC1") (pin "97") (pinfunction "PE0_97") (pintype "bidirectional"))
    )
    (net (code "109") (name "unconnected-(IC1-PE1-Pad98)") (class "Default")
      (node (ref "IC1") (pin "98") (pinfunction "PE1_98") (pintype "bidirectional"))
    )
    (net (code "110") (name "unconnected-(IC1-PE15-Pad46)") (class "Default")
      (node (ref "IC1") (pin "46") (pinfunction "PE15_46") (pintype "bidirectional"))
    )
    (net (code "111") (name "unconnected-(MIDI_IN-Pad1)") (class "Default")
      (node (ref "MIDI_IN") (pin "1") (pinfunction "1_1") (pintype "passive"))
    )
    (net (code "112") (name "unconnected-(MIDI_IN-Pad3)") (class "Default")
      (node (ref "MIDI_IN") (pin "3") (pinfunction "3_3") (pintype "passive"))
    )
    (net (code "113") (name "unconnected-(MIDI_OUT-Pad1)") (class "Default")
      (node (ref "MIDI_OUT") (pin "1") (pinfunction "1_1") (pintype "passive"))
    )
    (net (code "114") (name "unconnected-(MIDI_OUT-Pad3)") (class "Default")
      (node (ref "MIDI_OUT") (pin "3") (pinfunction "3_3") (pintype "passive"))
    )
    (net (code "115") (name "unconnected-(TC1-Pad7)") (class "Default")
      (node (ref "TC1") (pin "7") (pinfunction "7_7") (pintype "passive"))
    )
  )
)
